# DASH.net
KiCad netlist of a schematic drawn in Altium Designer
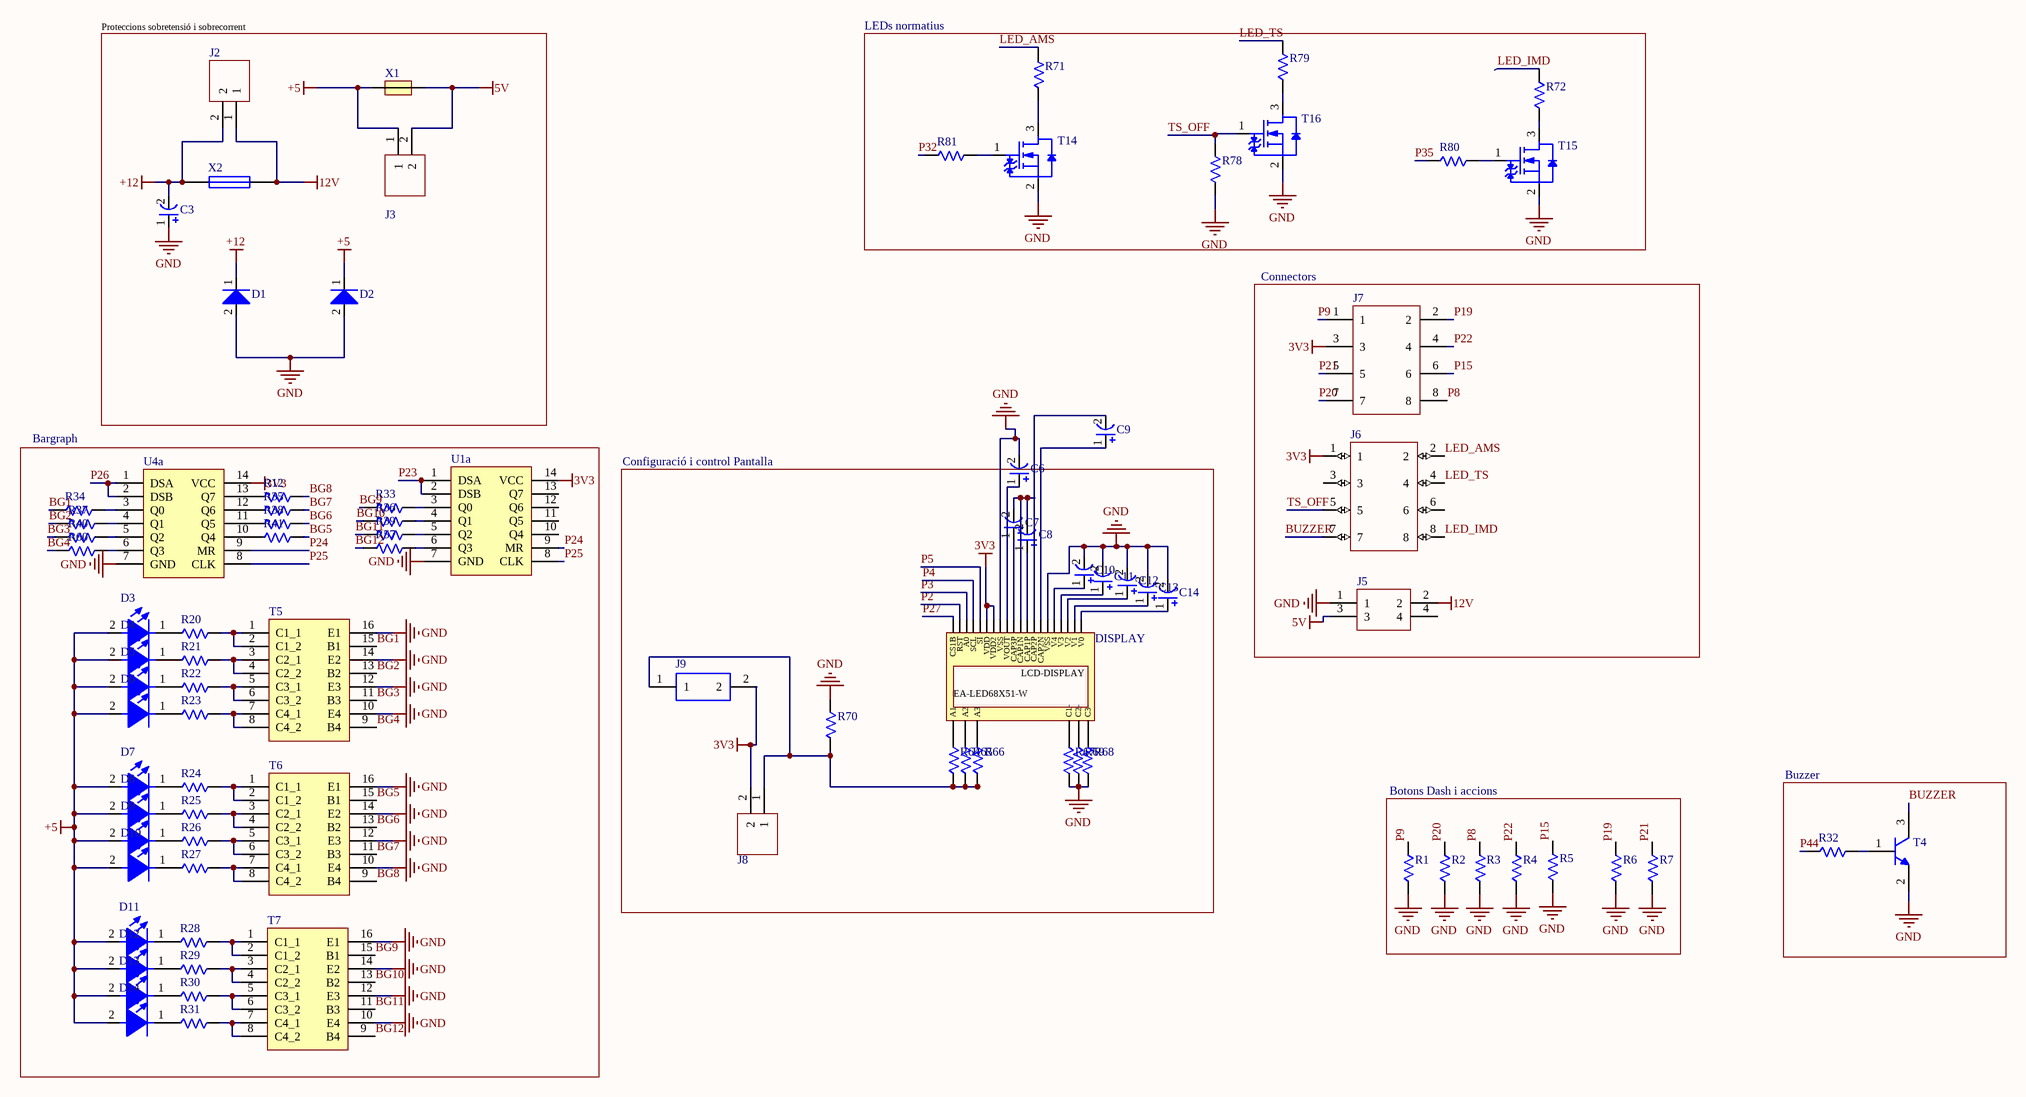
[diagram p0: DASH.SchDoc]

(export (version "E")
  (design (tool "Eeschema 10.0.6"))
  (components
    (comp (ref "C3")
      (value "TAJA105K020RNJ")
      (footprint "Chip2PinSM127P600-8N(condensador)")
      (description "CAP TANT 100nF 20V 10% 1206")
      (fields (field (name "TOLERANCE") "20%") (field (name "VOLTAGE") "20V"))
      (libsource (lib "DASH1_Schlib1") (part "CONDENSADOR 100nF"))
    )
    (comp (ref "C6")
      (value "TAJA105K020RNJ")
      (footprint "Chip2PinSM127P600-8N(condensador)")
      (description "CAP TANT 1uF 20V 10% 1206")
      (fields (field (name "TOLERANCE") "20%") (field (name "VOLTAGE") "20V"))
      (libsource (lib "DASH1_Schlib1") (part "CONDENSADOR 1uF"))
    )
    (comp (ref "C7")
      (value "TAJA105K020RNJ")
      (footprint "Chip2PinSM127P600-8N(condensador)")
      (description "CAP TANT 1uF 20V 10% 1206")
      (fields (field (name "TOLERANCE") "20%") (field (name "VOLTAGE") "20V"))
      (libsource (lib "DASH1_Schlib1") (part "CONDENSADOR 1uF"))
    )
    (comp (ref "C8")
      (value "TAJA105K020RNJ")
      (footprint "Chip2PinSM127P600-8N(condensador)")
      (description "CAP TANT 1uF 20V 10% 1206")
      (fields (field (name "TOLERANCE") "20%") (field (name "VOLTAGE") "20V"))
      (libsource (lib "DASH1_Schlib1") (part "CONDENSADOR 1uF"))
    )
    (comp (ref "C9")
      (value "TAJA105K020RNJ")
      (footprint "Chip2PinSM127P600-8N(condensador)")
      (description "CAP TANT 1uF 20V 10% 1206")
      (fields (field (name "TOLERANCE") "20%") (field (name "VOLTAGE") "20V"))
      (libsource (lib "DASH1_Schlib1") (part "CONDENSADOR 1uF"))
    )
    (comp (ref "C10")
      (value "TAJA105K020RNJ")
      (footprint "Chip2PinSM127P600-8N(condensador)")
      (description "CAP TANT 1uF 20V 10% 1206")
      (fields (field (name "TOLERANCE") "20%") (field (name "VOLTAGE") "20V"))
      (libsource (lib "DASH1_Schlib1") (part "CONDENSADOR 1uF"))
    )
    (comp (ref "C11")
      (value "TAJA105K020RNJ")
      (footprint "Chip2PinSM127P600-8N(condensador)")
      (description "CAP TANT 1uF 20V 10% 1206")
      (fields (field (name "TOLERANCE") "20%") (field (name "VOLTAGE") "20V"))
      (libsource (lib "DASH1_Schlib1") (part "CONDENSADOR 1uF"))
    )
    (comp (ref "C12")
      (value "TAJA105K020RNJ")
      (footprint "Chip2PinSM127P600-8N(condensador)")
      (description "CAP TANT 1uF 20V 10% 1206")
      (fields (field (name "TOLERANCE") "20%") (field (name "VOLTAGE") "20V"))
      (libsource (lib "DASH1_Schlib1") (part "CONDENSADOR 1uF"))
    )
    (comp (ref "C13")
      (value "TAJA105K020RNJ")
      (footprint "Chip2PinSM127P600-8N(condensador)")
      (description "CAP TANT 1uF 20V 10% 1206")
      (fields (field (name "TOLERANCE") "20%") (field (name "VOLTAGE") "20V"))
      (libsource (lib "DASH1_Schlib1") (part "CONDENSADOR 1uF"))
    )
    (comp (ref "C14")
      (value "TAJA105K020RNJ")
      (footprint "Chip2PinSM127P600-8N(condensador)")
      (description "CAP TANT 1uF 20V 10% 1206")
      (fields (field (name "TOLERANCE") "20%") (field (name "VOLTAGE") "20V"))
      (libsource (lib "DASH1_Schlib1") (part "CONDENSADOR 1uF"))
    )
    (comp (ref "D1")
      (value "SMAJ12CA")
      (footprint "Diode")
      (description "TVS DIODE 12V 19.9V DO214AC")
      (libsource (lib "DASH1_Schlib1") (part "DIODE"))
    )
    (comp (ref "D2")
      (value "SMAJ12CA")
      (footprint "Diode")
      (description "TVS DIODE 12V 19.9V DO214AC")
      (libsource (lib "DASH1_Schlib1") (part "DIODE"))
    )
    (comp (ref "D3")
      (value "150141GS73100")
      (footprint "Chip2PinSM127P600-8N(Buzz)")
      (description "WURTH ELEKTRONIK   150141GS73100   LED, 1411, GREEN, 1000MCD, 525NM")
      (libsource (lib "DASH1_Schlib1") (part "LED"))
    )
    (comp (ref "D4")
      (value "150141GS73100")
      (footprint "Chip2PinSM127P600-8N(Buzz)")
      (description "WURTH ELEKTRONIK   150141GS73100   LED, 1411, GREEN, 1000MCD, 525NM")
      (libsource (lib "DASH1_Schlib1") (part "LED"))
    )
    (comp (ref "D5")
      (value "150141GS73100")
      (footprint "Chip2PinSM127P600-8N(Buzz)")
      (description "WURTH ELEKTRONIK   150141GS73100   LED, 1411, GREEN, 1000MCD, 525NM")
      (libsource (lib "DASH1_Schlib1") (part "LED"))
    )
    (comp (ref "D6")
      (value "150141GS73100")
      (footprint "Chip2PinSM127P600-8N(Buzz)")
      (description "WURTH ELEKTRONIK   150141GS73100   LED, 1411, GREEN, 1000MCD, 525NM")
      (libsource (lib "DASH1_Schlib1") (part "LED"))
    )
    (comp (ref "D7")
      (value "150141GS73100")
      (footprint "Chip2PinSM127P600-8N(Buzz)")
      (description "WURTH ELEKTRONIK   150141GS73100   LED, 1411, GREEN, 1000MCD, 525NM")
      (libsource (lib "DASH1_Schlib1") (part "LED"))
    )
    (comp (ref "D8")
      (value "150141GS73100")
      (footprint "Chip2PinSM127P600-8N(Buzz)")
      (description "WURTH ELEKTRONIK   150141GS73100   LED, 1411, GREEN, 1000MCD, 525NM")
      (libsource (lib "DASH1_Schlib1") (part "LED"))
    )
    (comp (ref "D9")
      (value "150141GS73100")
      (footprint "Chip2PinSM127P600-8N(Buzz)")
      (description "WURTH ELEKTRONIK   150141GS73100   LED, 1411, GREEN, 1000MCD, 525NM")
      (libsource (lib "DASH1_Schlib1") (part "LED"))
    )
    (comp (ref "D10")
      (value "150141GS73100")
      (footprint "Chip2PinSM127P600-8N(Buzz)")
      (description "WURTH ELEKTRONIK   150141GS73100   LED, 1411, GREEN, 1000MCD, 525NM")
      (libsource (lib "DASH1_Schlib1") (part "LED"))
    )
    (comp (ref "D11")
      (value "150141GS73100")
      (footprint "Chip2PinSM127P600-8N(Buzz)")
      (description "WURTH ELEKTRONIK   150141GS73100   LED, 1411, GREEN, 1000MCD, 525NM")
      (libsource (lib "DASH1_Schlib1") (part "LED"))
    )
    (comp (ref "D12")
      (value "150141GS73100")
      (footprint "Chip2PinSM127P600-8N(Buzz)")
      (description "WURTH ELEKTRONIK   150141GS73100   LED, 1411, GREEN, 1000MCD, 525NM")
      (libsource (lib "DASH1_Schlib1") (part "LED"))
    )
    (comp (ref "D13")
      (value "150141GS73100")
      (footprint "Chip2PinSM127P600-8N(Buzz)")
      (description "WURTH ELEKTRONIK   150141GS73100   LED, 1411, GREEN, 1000MCD, 525NM")
      (libsource (lib "DASH1_Schlib1") (part "LED"))
    )
    (comp (ref "D14")
      (value "150141GS73100")
      (footprint "Chip2PinSM127P600-8N(Buzz)")
      (description "WURTH ELEKTRONIK   150141GS73100   LED, 1411, GREEN, 1000MCD, 525NM")
      (libsource (lib "DASH1_Schlib1") (part "LED"))
    )
    (comp (ref "DISPLAY")
      (value "M20-7820442")
      (footprint "DISPLAY")
      (description "2.54mm (0.1\") Pitch SIL Vertical PC Tail Socket Assembly, selective gold + tin, 4 contacts")
      (libsource (lib "DASH1_Schlib1") (part "DISPLAY"))
    )
    (comp (ref "J2")
      (value "68001-202HLF")
      (footprint "J2")
      (description "CONN HEADER VERT 2POS 2.54MM")
      (libsource (lib "") (part "HEADER_1"))
    )
    (comp (ref "J3")
      (value "68001-202HLF")
      (footprint "J3")
      (description "CONN HEADER VERT 2POS 2.54MM")
      (libsource (lib "DASH1_Schlib1") (part "HEADER"))
    )
    (comp (ref "J5")
      (value "1053141104")
      (footprint "J5")
      (description "NANO-FIT RIGHT ANGLE HEADER, TH")
      (libsource (lib "DASH1_Schlib1") (part "HEADER_J5"))
    )
    (comp (ref "J6")
      (value "43045-0800")
      (footprint "J6")
      (description "CONN HEADER R/A 8POS 3MM")
      (libsource (lib "DASH1_Schlib1") (part "HEADER_J6"))
    )
    (comp (ref "J7")
      (value "105314-1108")
      (footprint "J7")
      (description "Conn Power HDR 8 POS 2.5mm Solder RA Thru-Hole 8 Terminal 1 Port Nano-Fit Tray")
      (libsource (lib "DASH1_Schlib1") (part "HEADER_J7"))
    )
    (comp (ref "J8")
      (value "68001-202HLF")
      (footprint "J8")
      (description "CONN HEADER VERT 2POS 2.54MM")
      (libsource (lib "") (part "HEADER_2"))
    )
    (comp (ref "J9")
      (value "105313-1202")
      (footprint "J9")
      (description "CONN HEADER R/A 2POS 2.5MM")
      (libsource (lib "DASH1_Schlib1") (part "HEADER_J9"))
    )
    (comp (ref "R1")
      (value "CRCW120610K0JNTA-ND")
      (footprint "ERJ-8GEYJ102V")
      (description "RES SMD 10K OHM 5% 1/4W 1206")
      (fields (field (name "TOLERANCE") "5%"))
      (libsource (lib "DASH1_Schlib1") (part "RESISTOR 10K"))
    )
    (comp (ref "R2")
      (value "CRCW120610K0JNTA-ND")
      (footprint "ERJ-8GEYJ102V")
      (description "RES SMD 10K OHM 5% 1/4W 1206")
      (fields (field (name "TOLERANCE") "5%"))
      (libsource (lib "DASH1_Schlib1") (part "RESISTOR 10K"))
    )
    (comp (ref "R3")
      (value "CRCW120610K0JNTA-ND")
      (footprint "ERJ-8GEYJ102V")
      (description "RES SMD 10K OHM 5% 1/4W 1206")
      (fields (field (name "TOLERANCE") "5%"))
      (libsource (lib "DASH1_Schlib1") (part "RESISTOR 10K"))
    )
    (comp (ref "R4")
      (value "CRCW120610K0JNTA-ND")
      (footprint "ERJ-8GEYJ102V")
      (description "RES SMD 10K OHM 5% 1/4W 1206")
      (fields (field (name "TOLERANCE") "5%"))
      (libsource (lib "DASH1_Schlib1") (part "RESISTOR 10K"))
    )
    (comp (ref "R5")
      (value "CRCW120610K0JNTA-ND")
      (footprint "ERJ-8GEYJ102V")
      (description "RES SMD 10K OHM 5% 1/4W 1206")
      (fields (field (name "TOLERANCE") "5%"))
      (libsource (lib "DASH1_Schlib1") (part "RESISTOR 10K"))
    )
    (comp (ref "R6")
      (value "CRCW120610K0JNTA-ND")
      (footprint "ERJ-8GEYJ102V")
      (description "RES SMD 10K OHM 5% 1/4W 1206")
      (fields (field (name "TOLERANCE") "5%"))
      (libsource (lib "DASH1_Schlib1") (part "RESISTOR 10K"))
    )
    (comp (ref "R7")
      (value "CRCW120610K0JNTA-ND")
      (footprint "ERJ-8GEYJ102V")
      (description "RES SMD 10K OHM 5% 1/4W 1206")
      (fields (field (name "TOLERANCE") "5%"))
      (libsource (lib "DASH1_Schlib1") (part "RESISTOR 10K"))
    )
    (comp (ref "R12")
      (value "ERJ-8GEYJ102V")
      (footprint "ERJ-8GEYJ102V")
      (description "Res Thick Film 1206(3216) 1K Ohm 5% 1/4W 200ppm/C Molded SMD Punched Carrier T/R")
      (fields (field (name "TOLERANCE") "5%"))
      (libsource (lib "DASH1_Schlib1") (part "RESISTOR 1K"))
    )
    (comp (ref "R20")
      (value "ERJ-8GEYJ151V")
      (footprint "ERJ-8GEYJ102V")
      (description "RES SMD 150 OHM 5% 1/4W 1206")
      (fields (field (name "TOLERANCE") "5%"))
      (libsource (lib "DASH1_Schlib1") (part "RESISTOR 150R"))
    )
    (comp (ref "R21")
      (value "ERJ-8GEYJ151V")
      (footprint "ERJ-8GEYJ102V")
      (description "RES SMD 150 OHM 5% 1/4W 1206")
      (fields (field (name "TOLERANCE") "5%"))
      (libsource (lib "DASH1_Schlib1") (part "RESISTOR 150R"))
    )
    (comp (ref "R22")
      (value "ERJ-8GEYJ151V")
      (footprint "ERJ-8GEYJ102V")
      (description "RES SMD 150 OHM 5% 1/4W 1206")
      (fields (field (name "TOLERANCE") "5%"))
      (libsource (lib "DASH1_Schlib1") (part "RESISTOR 150R"))
    )
    (comp (ref "R23")
      (value "ERJ-8GEYJ151V")
      (footprint "ERJ-8GEYJ102V")
      (description "RES SMD 150 OHM 5% 1/4W 1206")
      (fields (field (name "TOLERANCE") "5%"))
      (libsource (lib "DASH1_Schlib1") (part "RESISTOR 150R"))
    )
    (comp (ref "R24")
      (value "ERJ-8GEYJ151V")
      (footprint "ERJ-8GEYJ102V")
      (description "RES SMD 150 OHM 5% 1/4W 1206")
      (fields (field (name "TOLERANCE") "5%"))
      (libsource (lib "DASH1_Schlib1") (part "RESISTOR 150R"))
    )
    (comp (ref "R25")
      (value "ERJ-8GEYJ151V")
      (footprint "ERJ-8GEYJ102V")
      (description "RES SMD 150 OHM 5% 1/4W 1206")
      (fields (field (name "TOLERANCE") "5%"))
      (libsource (lib "DASH1_Schlib1") (part "RESISTOR 150R"))
    )
    (comp (ref "R26")
      (value "ERJ-8GEYJ151V")
      (footprint "ERJ-8GEYJ102V")
      (description "RES SMD 150 OHM 5% 1/4W 1206")
      (fields (field (name "TOLERANCE") "5%"))
      (libsource (lib "DASH1_Schlib1") (part "RESISTOR 150R"))
    )
    (comp (ref "R27")
      (value "ERJ-8GEYJ151V")
      (footprint "ERJ-8GEYJ102V")
      (description "RES SMD 150 OHM 5% 1/4W 1206")
      (fields (field (name "TOLERANCE") "5%"))
      (libsource (lib "DASH1_Schlib1") (part "RESISTOR 150R"))
    )
    (comp (ref "R28")
      (value "ERJ-8GEYJ151V")
      (footprint "ERJ-8GEYJ102V")
      (description "RES SMD 150 OHM 5% 1/4W 1206")
      (fields (field (name "TOLERANCE") "5%"))
      (libsource (lib "DASH1_Schlib1") (part "RESISTOR 150R"))
    )
    (comp (ref "R29")
      (value "ERJ-8GEYJ151V")
      (footprint "ERJ-8GEYJ102V")
      (description "RES SMD 150 OHM 5% 1/4W 1206")
      (fields (field (name "TOLERANCE") "5%"))
      (libsource (lib "DASH1_Schlib1") (part "RESISTOR 150R"))
    )
    (comp (ref "R30")
      (value "ERJ-8GEYJ151V")
      (footprint "ERJ-8GEYJ102V")
      (description "RES SMD 150 OHM 5% 1/4W 1206")
      (fields (field (name "TOLERANCE") "5%"))
      (libsource (lib "DASH1_Schlib1") (part "RESISTOR 150R"))
    )
    (comp (ref "R31")
      (value "ERJ-8GEYJ151V")
      (footprint "ERJ-8GEYJ102V")
      (description "RES SMD 150 OHM 5% 1/4W 1206")
      (fields (field (name "TOLERANCE") "5%"))
      (libsource (lib "DASH1_Schlib1") (part "RESISTOR 150R"))
    )
    (comp (ref "R32")
      (value "ERJ-8GEYJ102V")
      (footprint "ERJ-8GEYJ102V")
      (description "Res Thick Film 1206(3216) 1K Ohm 5% 1/4W 200ppm/C Molded SMD Punched Carrier T/R")
      (fields (field (name "TOLERANCE") "5%"))
      (libsource (lib "DASH1_Schlib1") (part "RESISTOR 1K"))
    )
    (comp (ref "R33")
      (value "ERJ-8GEYJ102V")
      (footprint "ERJ-8GEYJ102V")
      (description "Res Thick Film 1206(3216) 1K Ohm 5% 1/4W 200ppm/C Molded SMD Punched Carrier T/R")
      (fields (field (name "TOLERANCE") "5%"))
      (libsource (lib "DASH1_Schlib1") (part "RESISTOR 1K"))
    )
    (comp (ref "R34")
      (value "ERJ-8GEYJ102V")
      (footprint "ERJ-8GEYJ102V")
      (description "Res Thick Film 1206(3216) 1K Ohm 5% 1/4W 200ppm/C Molded SMD Punched Carrier T/R")
      (fields (field (name "TOLERANCE") "5%"))
      (libsource (lib "DASH1_Schlib1") (part "RESISTOR 1K"))
    )
    (comp (ref "R35")
      (value "ERJ-8GEYJ102V")
      (footprint "ERJ-8GEYJ102V")
      (description "Res Thick Film 1206(3216) 1K Ohm 5% 1/4W 200ppm/C Molded SMD Punched Carrier T/R")
      (fields (field (name "TOLERANCE") "5%"))
      (libsource (lib "DASH1_Schlib1") (part "RESISTOR 1K"))
    )
    (comp (ref "R36")
      (value "ERJ-8GEYJ102V")
      (footprint "ERJ-8GEYJ102V")
      (description "Res Thick Film 1206(3216) 1K Ohm 5% 1/4W 200ppm/C Molded SMD Punched Carrier T/R")
      (fields (field (name "TOLERANCE") "5%"))
      (libsource (lib "DASH1_Schlib1") (part "RESISTOR 1K"))
    )
    (comp (ref "R37")
      (value "ERJ-8GEYJ102V")
      (footprint "ERJ-8GEYJ102V")
      (description "Res Thick Film 1206(3216) 1K Ohm 5% 1/4W 200ppm/C Molded SMD Punched Carrier T/R")
      (fields (field (name "TOLERANCE") "5%"))
      (libsource (lib "DASH1_Schlib1") (part "RESISTOR 1K"))
    )
    (comp (ref "R38")
      (value "ERJ-8GEYJ102V")
      (footprint "ERJ-8GEYJ102V")
      (description "Res Thick Film 1206(3216) 1K Ohm 5% 1/4W 200ppm/C Molded SMD Punched Carrier T/R")
      (fields (field (name "TOLERANCE") "5%"))
      (libsource (lib "DASH1_Schlib1") (part "RESISTOR 1K"))
    )
    (comp (ref "R39")
      (value "ERJ-8GEYJ102V")
      (footprint "ERJ-8GEYJ102V")
      (description "Res Thick Film 1206(3216) 1K Ohm 5% 1/4W 200ppm/C Molded SMD Punched Carrier T/R")
      (fields (field (name "TOLERANCE") "5%"))
      (libsource (lib "DASH1_Schlib1") (part "RESISTOR 1K"))
    )
    (comp (ref "R40")
      (value "ERJ-8GEYJ102V")
      (footprint "ERJ-8GEYJ102V")
      (description "Res Thick Film 1206(3216) 1K Ohm 5% 1/4W 200ppm/C Molded SMD Punched Carrier T/R")
      (fields (field (name "TOLERANCE") "5%"))
      (libsource (lib "DASH1_Schlib1") (part "RESISTOR 1K"))
    )
    (comp (ref "R41")
      (value "ERJ-8GEYJ102V")
      (footprint "ERJ-8GEYJ102V")
      (description "Res Thick Film 1206(3216) 1K Ohm 5% 1/4W 200ppm/C Molded SMD Punched Carrier T/R")
      (fields (field (name "TOLERANCE") "5%"))
      (libsource (lib "DASH1_Schlib1") (part "RESISTOR 1K"))
    )
    (comp (ref "R57")
      (value "ERJ-8GEYJ102V")
      (footprint "ERJ-8GEYJ102V")
      (description "Res Thick Film 1206(3216) 1K Ohm 5% 1/4W 200ppm/C Molded SMD Punched Carrier T/R")
      (fields (field (name "TOLERANCE") "5%"))
      (libsource (lib "DASH1_Schlib1") (part "RESISTOR 1K"))
    )
    (comp (ref "R60")
      (value "ERJ-8GEYJ102V")
      (footprint "ERJ-8GEYJ102V")
      (description "Res Thick Film 1206(3216) 1K Ohm 5% 1/4W 200ppm/C Molded SMD Punched Carrier T/R")
      (fields (field (name "TOLERANCE") "5%"))
      (libsource (lib "DASH1_Schlib1") (part "RESISTOR 1K"))
    )
    (comp (ref "R64")
      (value "ERJ-8GEYJ102V")
      (footprint "ERJ-8GEYJ102V")
      (description "Res Thick Film 1206(3216) 70 Ohm 5% 1/4W 200ppm/C Molded SMD Punched Carrier T/R")
      (fields (field (name "TOLERANCE") "5%"))
      (libsource (lib "DASH1_Schlib1") (part "RESISTOR 70R"))
    )
    (comp (ref "R65")
      (value "ERJ-8GEYJ102V")
      (footprint "ERJ-8GEYJ102V")
      (description "Res Thick Film 1206(3216) 70 Ohm 5% 1/4W 200ppm/C Molded SMD Punched Carrier T/R")
      (fields (field (name "TOLERANCE") "5%"))
      (libsource (lib "DASH1_Schlib1") (part "RESISTOR 70R"))
    )
    (comp (ref "R66")
      (value "ERJ-8GEYJ102V")
      (footprint "ERJ-8GEYJ102V")
      (description "Res Thick Film 1206(3216) 70 Ohm 5% 1/4W 200ppm/C Molded SMD Punched Carrier T/R")
      (fields (field (name "TOLERANCE") "5%"))
      (libsource (lib "DASH1_Schlib1") (part "RESISTOR 70R"))
    )
    (comp (ref "R67")
      (value "ERJ-8GEYJ102V")
      (footprint "ERJ-8GEYJ102V")
      (description "Res Thick Film 1206(3216) 70 Ohm 5% 1/4W 200ppm/C Molded SMD Punched Carrier T/R")
      (fields (field (name "TOLERANCE") "5%"))
      (libsource (lib "DASH1_Schlib1") (part "RESISTOR 70R"))
    )
    (comp (ref "R68")
      (value "ERJ-8GEYJ102V")
      (footprint "ERJ-8GEYJ102V")
      (description "Res Thick Film 1206(3216) 70 Ohm 5% 1/4W 200ppm/C Molded SMD Punched Carrier T/R")
      (fields (field (name "TOLERANCE") "5%"))
      (libsource (lib "DASH1_Schlib1") (part "RESISTOR 70R"))
    )
    (comp (ref "R69")
      (value "ERJ-8GEYJ102V")
      (footprint "ERJ-8GEYJ102V")
      (description "Res Thick Film 1206(3216) 70 Ohm 5% 1/4W 200ppm/C Molded SMD Punched Carrier T/R")
      (fields (field (name "TOLERANCE") "5%"))
      (libsource (lib "DASH1_Schlib1") (part "RESISTOR 70R"))
    )
    (comp (ref "R70")
      (value "CRCW120610K0JNTA-ND")
      (footprint "ERJ-8GEYJ102V")
      (description "RES SMD 10K OHM 5% 1/4W 1206")
      (fields (field (name "TOLERANCE") "5%"))
      (libsource (lib "DASH1_Schlib1") (part "RESISTOR 10K"))
    )
    (comp (ref "R71")
      (value "ERJ-8GEYJ151V")
      (footprint "ERJ-8GEYJ102V")
      (description "RES SMD 150 OHM 5% 1/4W 1206")
      (fields (field (name "TOLERANCE") "5%"))
      (libsource (lib "DASH1_Schlib1") (part "RESISTOR 150R"))
    )
    (comp (ref "R72")
      (value "ERJ-8GEYJ151V")
      (footprint "ERJ-8GEYJ102V")
      (description "RES SMD 150 OHM 5% 1/4W 1206")
      (fields (field (name "TOLERANCE") "5%"))
      (libsource (lib "DASH1_Schlib1") (part "RESISTOR 150R"))
    )
    (comp (ref "R78")
      (value "CRCW120610K0JNTA-ND")
      (footprint "ERJ-8GEYJ102V")
      (description "RES SMD 10K OHM 5% 1/4W 1206")
      (fields (field (name "TOLERANCE") "5%"))
      (libsource (lib "DASH1_Schlib1") (part "RESISTOR 10K"))
    )
    (comp (ref "R79")
      (value "ERJ-8GEYJ151V")
      (footprint "ERJ-8GEYJ102V")
      (description "RES SMD 150 OHM 5% 1/4W 1206")
      (fields (field (name "TOLERANCE") "5%"))
      (libsource (lib "DASH1_Schlib1") (part "RESISTOR 150R"))
    )
    (comp (ref "R80")
      (value "ERJ-8GEYJ102V")
      (footprint "ERJ-8GEYJ102V")
      (description "Res Thick Film 1206(3216) 1K Ohm 5% 1/4W 200ppm/C Molded SMD Punched Carrier T/R")
      (fields (field (name "TOLERANCE") "5%"))
      (libsource (lib "DASH1_Schlib1") (part "RESISTOR 1K"))
    )
    (comp (ref "R81")
      (value "ERJ-8GEYJ102V")
      (footprint "ERJ-8GEYJ102V")
      (description "Res Thick Film 1206(3216) 1K Ohm 5% 1/4W 200ppm/C Molded SMD Punched Carrier T/R")
      (fields (field (name "TOLERANCE") "5%"))
      (libsource (lib "DASH1_Schlib1") (part "RESISTOR 1K"))
    )
    (comp (ref "T4")
      (value "BC817-25LT1G")
      (footprint "SOT190P240X100-3N")
      (description "TRANS NPN 45V 0.5A SOT23")
      (libsource (lib "DASH1_Schlib1") (part "TRANSISTOR_BUZZ"))
    )
    (comp (ref "T5")
      (value "MMPQ2222A")
      (footprint "SOP127P600-8N(MMPQ2222A)")
      (description "TRANS 4NPN 40V 0.5A 16SOIC")
      (libsource (lib "DASH1_Schlib1") (part "MMPQ2222A"))
    )
    (comp (ref "T6")
      (value "MMPQ2222A")
      (footprint "SOP127P600-8N(MMPQ2222A)")
      (description "TRANS 4NPN 40V 0.5A 16SOIC")
      (libsource (lib "DASH1_Schlib1") (part "MMPQ2222A"))
    )
    (comp (ref "T7")
      (value "MMPQ2222A")
      (footprint "SOP127P600-8N(MMPQ2222A)")
      (description "TRANS 4NPN 40V 0.5A 16SOIC")
      (libsource (lib "DASH1_Schlib1") (part "MMPQ2222A"))
    )
    (comp (ref "T14")
      (value "CPH3455-TL-H")
      (footprint "SOT190P280X90-3N")
      (description "MOSFET N-CH 35V 3A CPH3")
      (libsource (lib "DASH1_Schlib1") (part "TRANSISTOR"))
    )
    (comp (ref "T15")
      (value "CPH3455-TL-H")
      (footprint "SOT190P280X90-3N")
      (description "MOSFET N-CH 35V 3A CPH3")
      (libsource (lib "DASH1_Schlib1") (part "TRANSISTOR"))
    )
    (comp (ref "T16")
      (value "CPH3455-TL-H")
      (footprint "SOT190P280X90-3N")
      (description "MOSFET N-CH 35V 3A CPH3")
      (libsource (lib "DASH1_Schlib1") (part "TRANSISTOR"))
    )
    (comp (ref "U1a")
      (value "SN74HC164D")
      (footprint "SOP127P600-8N")
      (description "IC, SHIFT REGISTER, SMD, 74HC164")
      (libsource (lib "DASH1_Schlib1") (part "SN74HC164D"))
    )
    (comp (ref "U4a")
      (value "SN74HC164D")
      (footprint "SOP127P600-8N")
      (description "IC, SHIFT REGISTER, SMD, 74HC164")
      (libsource (lib "DASH1_Schlib1") (part "SN74HC164D"))
    )
    (comp (ref "X1") (value "FUSE 3A") (footprint "Fuse") (libsource (lib "DASH1_Schlib1") (part "FUSE 3A")))
    (comp (ref "X2")
      (value "Fuse 1A")
      (footprint "Fuse")
      (description "Fuse")
      (fields (field (name "PUBLISHER") "Altium Limited"))
      (libsource (lib "Miscellaneous Devices") (part "Fuse 1"))
    )
  )
  (nets
    (net (code "1") (name "+5") (class "Default")
      (node (ref "D10") (pin "2") (pinfunction "ANODE_2") (pintype "passive"))
      (node (ref "D11") (pin "2") (pinfunction "ANODE_2") (pintype "passive"))
      (node (ref "D12") (pin "2") (pinfunction "ANODE_2") (pintype "passive"))
      (node (ref "D13") (pin "2") (pinfunction "ANODE_2") (pintype "passive"))
      (node (ref "D14") (pin "2") (pinfunction "ANODE_2") (pintype "passive"))
      (node (ref "D2") (pin "1") (pinfunction "catode_1") (pintype "passive"))
      (node (ref "D3") (pin "2") (pinfunction "ANODE_2") (pintype "passive"))
      (node (ref "D4") (pin "2") (pinfunction "ANODE_2") (pintype "passive"))
      (node (ref "D5") (pin "2") (pinfunction "ANODE_2") (pintype "passive"))
      (node (ref "D6") (pin "2") (pinfunction "ANODE_2") (pintype "passive"))
      (node (ref "D7") (pin "2") (pinfunction "ANODE_2") (pintype "passive"))
      (node (ref "D8") (pin "2") (pinfunction "ANODE_2") (pintype "passive"))
      (node (ref "D9") (pin "2") (pinfunction "ANODE_2") (pintype "passive"))
      (node (ref "J3") (pin "1") (pinfunction "1_1") (pintype "passive"))
      (node (ref "X1") (pin "1") (pinfunction "1_1") (pintype "passive"))
    )
    (net (code "2") (name "+12") (class "Default")
      (node (ref "C3") (pin "2") (pinfunction "2_2") (pintype "passive"))
      (node (ref "D1") (pin "1") (pinfunction "catode_1") (pintype "passive"))
      (node (ref "J2") (pin "2") (pinfunction "2_2") (pintype "passive"))
      (node (ref "X2") (pin "1") (pinfunction "1_1") (pintype "passive"))
    )
    (net (code "4") (name "/BG1") (class "Default")
      (node (ref "R34") (pin "1") (pinfunction "1_1") (pintype "passive"))
      (node (ref "T5") (pin "15") (pinfunction "B1_15") (pintype "passive"))
    )
    (net (code "5") (name "/BG2") (class "Default")
      (node (ref "R37") (pin "1") (pinfunction "1_1") (pintype "passive"))
      (node (ref "T5") (pin "13") (pinfunction "B2_13") (pintype "passive"))
    )
    (net (code "6") (name "/BG3") (class "Default")
      (node (ref "R40") (pin "1") (pinfunction "1_1") (pintype "passive"))
      (node (ref "T5") (pin "11") (pinfunction "B3_11") (pintype "passive"))
    )
    (net (code "7") (name "/BG4") (class "Default")
      (node (ref "R60") (pin "1") (pinfunction "1_1") (pintype "passive"))
      (node (ref "T5") (pin "9") (pinfunction "B4_9") (pintype "passive"))
    )
    (net (code "8") (name "/BG5") (class "Default")
      (node (ref "R41") (pin "2") (pinfunction "2_2") (pintype "passive"))
      (node (ref "T6") (pin "15") (pinfunction "B1_15") (pintype "passive"))
    )
    (net (code "9") (name "/BG6") (class "Default")
      (node (ref "R38") (pin "2") (pinfunction "2_2") (pintype "passive"))
      (node (ref "T6") (pin "13") (pinfunction "B2_13") (pintype "passive"))
    )
    (net (code "10") (name "/BG7") (class "Default")
      (node (ref "R35") (pin "2") (pinfunction "2_2") (pintype "passive"))
      (node (ref "T6") (pin "11") (pinfunction "B3_11") (pintype "passive"))
    )
    (net (code "11") (name "/BG8") (class "Default")
      (node (ref "R12") (pin "2") (pinfunction "2_2") (pintype "passive"))
      (node (ref "T6") (pin "9") (pinfunction "B4_9") (pintype "passive"))
    )
    (net (code "12") (name "/BG9") (class "Default")
      (node (ref "R33") (pin "1") (pinfunction "1_1") (pintype "passive"))
      (node (ref "T7") (pin "15") (pinfunction "B1_15") (pintype "passive"))
    )
    (net (code "13") (name "/BG10") (class "Default")
      (node (ref "R36") (pin "1") (pinfunction "1_1") (pintype "passive"))
      (node (ref "T7") (pin "13") (pinfunction "B2_13") (pintype "passive"))
    )
    (net (code "14") (name "/BG11") (class "Default")
      (node (ref "R39") (pin "1") (pinfunction "1_1") (pintype "passive"))
      (node (ref "T7") (pin "11") (pinfunction "B3_11") (pintype "passive"))
    )
    (net (code "15") (name "/BG12") (class "Default")
      (node (ref "R57") (pin "1") (pinfunction "1_1") (pintype "passive"))
      (node (ref "T7") (pin "9") (pinfunction "B4_9") (pintype "passive"))
    )
    (net (code "16") (name "/BUZZER") (class "Default")
      (node (ref "J6") (pin "7") (pinfunction "7_7") (pintype "bidirectional"))
      (node (ref "T4") (pin "3") (pinfunction "Collector_3") (pintype "passive"))
    )
    (net (code "17") (name "/LED_AMS") (class "Default")
      (node (ref "J6") (pin "2") (pinfunction "2_2") (pintype "bidirectional"))
      (node (ref "R71") (pin "2") (pinfunction "2_2") (pintype "passive"))
    )
    (net (code "18") (name "/LED_IMD") (class "Default")
      (node (ref "J6") (pin "8") (pinfunction "8_8") (pintype "bidirectional"))
      (node (ref "R72") (pin "2") (pinfunction "2_2") (pintype "passive"))
    )
    (net (code "19") (name "/LED_TS") (class "Default")
      (node (ref "J6") (pin "4") (pinfunction "4_4") (pintype "bidirectional"))
      (node (ref "R79") (pin "2") (pinfunction "2_2") (pintype "passive"))
    )
    (net (code "20") (name "/P2") (class "Default")
      (node (ref "DISPLAY") (pin "39") (pinfunction "RST_39") (pintype "passive"))
    )
    (net (code "21") (name "/P3") (class "Default")
      (node (ref "DISPLAY") (pin "38") (pinfunction "A0_38") (pintype "passive"))
    )
    (net (code "22") (name "/P4") (class "Default")
      (node (ref "DISPLAY") (pin "37") (pinfunction "SCL_37") (pintype "passive"))
    )
    (net (code "23") (name "/P5") (class "Default")
      (node (ref "DISPLAY") (pin "36") (pinfunction "SI_36") (pintype "passive"))
    )
    (net (code "24") (name "/P8") (class "Default")
      (node (ref "J7") (pin "8") (pinfunction "8_8") (pintype "passive"))
      (node (ref "R3") (pin "2") (pinfunction "2_2") (pintype "passive"))
    )
    (net (code "25") (name "/P9") (class "Default")
      (node (ref "J7") (pin "1") (pinfunction "1_1") (pintype "passive"))
      (node (ref "R1") (pin "2") (pinfunction "2_2") (pintype "passive"))
    )
    (net (code "26") (name "/P15") (class "Default")
      (node (ref "J7") (pin "6") (pinfunction "6_6") (pintype "passive"))
      (node (ref "R5") (pin "2") (pinfunction "2_2") (pintype "passive"))
    )
    (net (code "27") (name "/P19") (class "Default")
      (node (ref "J7") (pin "2") (pinfunction "2_2") (pintype "passive"))
      (node (ref "R6") (pin "2") (pinfunction "2_2") (pintype "passive"))
    )
    (net (code "28") (name "/P20") (class "Default")
      (node (ref "J7") (pin "7") (pinfunction "7_7") (pintype "passive"))
      (node (ref "R2") (pin "2") (pinfunction "2_2") (pintype "passive"))
    )
    (net (code "29") (name "/P21") (class "Default")
      (node (ref "J7") (pin "5") (pinfunction "5_5") (pintype "passive"))
      (node (ref "R7") (pin "2") (pinfunction "2_2") (pintype "passive"))
    )
    (net (code "30") (name "/P22") (class "Default")
      (node (ref "J7") (pin "4") (pinfunction "4_4") (pintype "passive"))
      (node (ref "R4") (pin "2") (pinfunction "2_2") (pintype "passive"))
    )
    (net (code "31") (name "/P23") (class "Default")
      (node (ref "U1a") (pin "1") (pinfunction "DSA_1") (pintype "passive"))
      (node (ref "U1a") (pin "2") (pinfunction "DSB_2") (pintype "passive"))
    )
    (net (code "32") (name "/P24") (class "Default")
      (node (ref "U1a") (pin "9") (pinfunction "MR_9") (pintype "passive"))
      (node (ref "U4a") (pin "9") (pinfunction "MR_9") (pintype "passive"))
    )
    (net (code "33") (name "/P25") (class "Default")
      (node (ref "U1a") (pin "8") (pinfunction "CLK_8") (pintype "passive"))
      (node (ref "U4a") (pin "8") (pinfunction "CLK_8") (pintype "passive"))
    )
    (net (code "34") (name "/P26") (class "Default")
      (node (ref "U4a") (pin "1") (pinfunction "DSA_1") (pintype "passive"))
      (node (ref "U4a") (pin "2") (pinfunction "DSB_2") (pintype "passive"))
    )
    (net (code "35") (name "/P27") (class "Default")
      (node (ref "DISPLAY") (pin "40") (pinfunction "CS1B_40") (pintype "passive"))
    )
    (net (code "36") (name "/P32") (class "Default")
      (node (ref "R81") (pin "1") (pinfunction "1_1") (pintype "passive"))
    )
    (net (code "37") (name "/P35") (class "Default")
      (node (ref "R80") (pin "1") (pinfunction "1_1") (pintype "passive"))
    )
    (net (code "38") (name "/P44") (class "Default")
      (node (ref "R32") (pin "1") (pinfunction "1_1") (pintype "passive"))
    )
    (net (code "39") (name "/TS_OFF") (class "Default")
      (node (ref "J6") (pin "5") (pinfunction "5_5") (pintype "bidirectional"))
      (node (ref "R78") (pin "2") (pinfunction "2_2") (pintype "passive"))
      (node (ref "T16") (pin "1") (pinfunction "Gate_1") (pintype "passive"))
    )
    (net (code "40") (name "3V3") (class "Default")
      (node (ref "DISPLAY") (pin "34") (pinfunction "VDD2_34") (pintype "passive"))
      (node (ref "DISPLAY") (pin "35") (pinfunction "VDD_35") (pintype "passive"))
      (node (ref "J6") (pin "1") (pinfunction "1_1") (pintype "bidirectional"))
      (node (ref "J7") (pin "3") (pinfunction "3_3") (pintype "passive"))
      (node (ref "J8") (pin "2") (pinfunction "2_2") (pintype "passive"))
      (node (ref "J9") (pin "2") (pinfunction "2_2") (pintype "passive"))
      (node (ref "U1a") (pin "14") (pinfunction "VCC_14") (pintype "power_in"))
      (node (ref "U4a") (pin "14") (pinfunction "VCC_14") (pintype "power_in"))
    )
    (net (code "41") (name "5V") (class "Default")
      (node (ref "J3") (pin "2") (pinfunction "2_2") (pintype "passive"))
      (node (ref "J5") (pin "3") (pinfunction "3_3") (pintype "passive"))
      (node (ref "X1") (pin "2") (pinfunction "2_2") (pintype "passive"))
    )
    (net (code "42") (name "12V") (class "Default")
      (node (ref "J2") (pin "1") (pinfunction "1_1") (pintype "passive"))
      (node (ref "J5") (pin "2") (pinfunction "2_2") (pintype "passive"))
      (node (ref "X2") (pin "2") (pinfunction "2_2") (pintype "passive"))
    )
    (net (code "43") (name "GND") (class "Default")
      (node (ref "C10") (pin "2") (pinfunction "2_2") (pintype "passive"))
      (node (ref "C11") (pin "2") (pinfunction "2_2") (pintype "passive"))
      (node (ref "C12") (pin "2") (pinfunction "2_2") (pintype "passive"))
      (node (ref "C13") (pin "2") (pinfunction "2_2") (pintype "passive"))
      (node (ref "C14") (pin "2") (pinfunction "2_2") (pintype "passive"))
      (node (ref "C3") (pin "1") (pinfunction "1_1") (pintype "passive"))
      (node (ref "C6") (pin "2") (pinfunction "2_2") (pintype "passive"))
      (node (ref "D1") (pin "2") (pinfunction "anode_2") (pintype "passive"))
      (node (ref "D2") (pin "2") (pinfunction "anode_2") (pintype "passive"))
      (node (ref "DISPLAY") (pin "26") (pinfunction "VSS_26") (pintype "passive"))
      (node (ref "DISPLAY") (pin "33") (pinfunction "VSS_33") (pintype "passive"))
      (node (ref "J5") (pin "1") (pinfunction "1_1") (pintype "passive"))
      (node (ref "R1") (pin "1") (pinfunction "1_1") (pintype "passive"))
      (node (ref "R2") (pin "1") (pinfunction "1_1") (pintype "passive"))
      (node (ref "R3") (pin "1") (pinfunction "1_1") (pintype "passive"))
      (node (ref "R4") (pin "1") (pinfunction "1_1") (pintype "passive"))
      (node (ref "R5") (pin "1") (pinfunction "1_1") (pintype "passive"))
      (node (ref "R6") (pin "1") (pinfunction "1_1") (pintype "passive"))
      (node (ref "R67") (pin "2") (pinfunction "2_2") (pintype "passive"))
      (node (ref "R68") (pin "2") (pinfunction "2_2") (pintype "passive"))
      (node (ref "R69") (pin "2") (pinfunction "2_2") (pintype "passive"))
      (node (ref "R7") (pin "1") (pinfunction "1_1") (pintype "passive"))
      (node (ref "R70") (pin "2") (pinfunction "2_2") (pintype "passive"))
      (node (ref "R78") (pin "1") (pinfunction "1_1") (pintype "passive"))
      (node (ref "T14") (pin "2") (pinfunction "Source_2") (pintype "passive"))
      (node (ref "T15") (pin "2") (pinfunction "Source_2") (pintype "passive"))
      (node (ref "T16") (pin "2") (pinfunction "Source_2") (pintype "passive"))
      (node (ref "T4") (pin "2") (pinfunction "Emitter_2") (pintype "passive"))
      (node (ref "T5") (pin "10") (pinfunction "E4_10") (pintype "passive"))
      (node (ref "T5") (pin "12") (pinfunction "E3_12") (pintype "passive"))
      (node (ref "T5") (pin "14") (pinfunction "E2_14") (pintype "passive"))
      (node (ref "T5") (pin "16") (pinfunction "E1_16") (pintype "passive"))
      (node (ref "T6") (pin "10") (pinfunction "E4_10") (pintype "passive"))
      (node (ref "T6") (pin "12") (pinfunction "E3_12") (pintype "passive"))
      (node (ref "T6") (pin "14") (pinfunction "E2_14") (pintype "passive"))
      (node (ref "T6") (pin "16") (pinfunction "E1_16") (pintype "passive"))
      (node (ref "T7") (pin "10") (pinfunction "E4_10") (pintype "passive"))
      (node (ref "T7") (pin "12") (pinfunction "E3_12") (pintype "passive"))
      (node (ref "T7") (pin "14") (pinfunction "E2_14") (pintype "passive"))
      (node (ref "T7") (pin "16") (pinfunction "E1_16") (pintype "passive"))
      (node (ref "U1a") (pin "7") (pinfunction "GND_7") (pintype "passive"))
      (node (ref "U4a") (pin "7") (pinfunction "GND_7") (pintype "passive"))
    )
    (net (code "44") (name "Net-(D3-CATODE)") (class "Default")
      (node (ref "D3") (pin "1") (pinfunction "CATODE_1") (pintype "passive"))
      (node (ref "R20") (pin "1") (pinfunction "1_1") (pintype "passive"))
    )
    (net (code "45") (name "Net-(D4-CATODE)") (class "Default")
      (node (ref "D4") (pin "1") (pinfunction "CATODE_1") (pintype "passive"))
      (node (ref "R21") (pin "1") (pinfunction "1_1") (pintype "passive"))
    )
    (net (code "46") (name "Net-(D5-CATODE)") (class "Default")
      (node (ref "D5") (pin "1") (pinfunction "CATODE_1") (pintype "passive"))
      (node (ref "R22") (pin "1") (pinfunction "1_1") (pintype "passive"))
    )
    (net (code "47") (name "Net-(D6-CATODE)") (class "Default")
      (node (ref "D6") (pin "1") (pinfunction "CATODE_1") (pintype "passive"))
      (node (ref "R23") (pin "1") (pinfunction "1_1") (pintype "passive"))
    )
    (net (code "48") (name "Net-(D7-CATODE)") (class "Default")
      (node (ref "D7") (pin "1") (pinfunction "CATODE_1") (pintype "passive"))
      (node (ref "R24") (pin "1") (pinfunction "1_1") (pintype "passive"))
    )
    (net (code "49") (name "Net-(D8-CATODE)") (class "Default")
      (node (ref "D8") (pin "1") (pinfunction "CATODE_1") (pintype "passive"))
      (node (ref "R25") (pin "1") (pinfunction "1_1") (pintype "passive"))
    )
    (net (code "50") (name "Net-(D9-CATODE)") (class "Default")
      (node (ref "D9") (pin "1") (pinfunction "CATODE_1") (pintype "passive"))
      (node (ref "R26") (pin "1") (pinfunction "1_1") (pintype "passive"))
    )
    (net (code "51") (name "Net-(D10-CATODE)") (class "Default")
      (node (ref "D10") (pin "1") (pinfunction "CATODE_1") (pintype "passive"))
      (node (ref "R27") (pin "1") (pinfunction "1_1") (pintype "passive"))
    )
    (net (code "52") (name "Net-(D11-CATODE)") (class "Default")
      (node (ref "D11") (pin "1") (pinfunction "CATODE_1") (pintype "passive"))
      (node (ref "R28") (pin "1") (pinfunction "1_1") (pintype "passive"))
    )
    (net (code "53") (name "Net-(D12-CATODE)") (class "Default")
      (node (ref "D12") (pin "1") (pinfunction "CATODE_1") (pintype "passive"))
      (node (ref "R29") (pin "1") (pinfunction "1_1") (pintype "passive"))
    )
    (net (code "54") (name "Net-(D13-CATODE)") (class "Default")
      (node (ref "D13") (pin "1") (pinfunction "CATODE_1") (pintype "passive"))
      (node (ref "R30") (pin "1") (pinfunction "1_1") (pintype "passive"))
    )
    (net (code "55") (name "Net-(D14-CATODE)") (class "Default")
      (node (ref "D14") (pin "1") (pinfunction "CATODE_1") (pintype "passive"))
      (node (ref "R31") (pin "1") (pinfunction "1_1") (pintype "passive"))
    )
    (net (code "56") (name "Net-(DISPLAY-A1)") (class "Default")
      (node (ref "DISPLAY") (pin "41") (pinfunction "A1_41") (pintype "passive"))
      (node (ref "R64") (pin "2") (pinfunction "2_2") (pintype "passive"))
    )
    (net (code "57") (name "Net-(DISPLAY-A2)") (class "Default")
      (node (ref "DISPLAY") (pin "42") (pinfunction "A2_42") (pintype "passive"))
      (node (ref "R65") (pin "2") (pinfunction "2_2") (pintype "passive"))
    )
    (net (code "58") (name "Net-(DISPLAY-A3)") (class "Default")
      (node (ref "DISPLAY") (pin "43") (pinfunction "A3_43") (pintype "passive"))
      (node (ref "R66") (pin "2") (pinfunction "2_2") (pintype "passive"))
    )
    (net (code "59") (name "Net-(DISPLAY-C1-)") (class "Default")
      (node (ref "DISPLAY") (pin "46") (pinfunction "C1-_46") (pintype "passive"))
      (node (ref "R67") (pin "1") (pinfunction "1_1") (pintype "passive"))
    )
    (net (code "60") (name "Net-(DISPLAY-C2-)") (class "Default")
      (node (ref "DISPLAY") (pin "45") (pinfunction "C2-_45") (pintype "passive"))
      (node (ref "R69") (pin "1") (pinfunction "1_1") (pintype "passive"))
    )
    (net (code "61") (name "Net-(DISPLAY-C3-)") (class "Default")
      (node (ref "DISPLAY") (pin "44") (pinfunction "C3-_44") (pintype "passive"))
      (node (ref "R68") (pin "1") (pinfunction "1_1") (pintype "passive"))
    )
    (net (code "62") (name "Net-(DISPLAY-CAP1N)") (class "Default")
      (node (ref "C7") (pin "2") (pinfunction "2_2") (pintype "passive"))
      (node (ref "C8") (pin "2") (pinfunction "2_2") (pintype "passive"))
      (node (ref "DISPLAY") (pin "30") (pinfunction "CAP1N_30") (pintype "passive"))
    )
    (net (code "63") (name "Net-(DISPLAY-CAP1P)") (class "Default")
      (node (ref "C8") (pin "1") (pinfunction "1_1") (pintype "passive"))
      (node (ref "DISPLAY") (pin "29") (pinfunction "CAP1P_29") (pintype "passive"))
    )
    (net (code "64") (name "Net-(DISPLAY-CAP2N)") (class "Default")
      (node (ref "C9") (pin "1") (pinfunction "1_1") (pintype "passive"))
      (node (ref "DISPLAY") (pin "27") (pinfunction "CAP2N_27") (pintype "passive"))
    )
    (net (code "65") (name "Net-(DISPLAY-CAP2P)") (class "Default")
      (node (ref "C9") (pin "2") (pinfunction "2_2") (pintype "passive"))
      (node (ref "DISPLAY") (pin "28") (pinfunction "CAP2P_28") (pintype "passive"))
    )
    (net (code "66") (name "Net-(DISPLAY-CAP3P)") (class "Default")
      (node (ref "C7") (pin "1") (pinfunction "1_1") (pintype "passive"))
      (node (ref "DISPLAY") (pin "31") (pinfunction "CAP3P_31") (pintype "passive"))
    )
    (net (code "67") (name "Net-(DISPLAY-V0)") (class "Default")
      (node (ref "C14") (pin "1") (pinfunction "1_1") (pintype "passive"))
      (node (ref "DISPLAY") (pin "21") (pinfunction "V0_21") (pintype "passive"))
    )
    (net (code "68") (name "Net-(DISPLAY-V1)") (class "Default")
      (node (ref "C13") (pin "1") (pinfunction "1_1") (pintype "passive"))
      (node (ref "DISPLAY") (pin "22") (pinfunction "V1_22") (pintype "passive"))
    )
    (net (code "69") (name "Net-(DISPLAY-V2)") (class "Default")
      (node (ref "C12") (pin "1") (pinfunction "1_1") (pintype "passive"))
      (node (ref "DISPLAY") (pin "23") (pinfunction "V2_23") (pintype "passive"))
    )
    (net (code "70") (name "Net-(DISPLAY-V3)") (class "Default")
      (node (ref "C11") (pin "1") (pinfunction "1_1") (pintype "passive"))
      (node (ref "DISPLAY") (pin "24") (pinfunction "V3_24") (pintype "passive"))
    )
    (net (code "71") (name "Net-(DISPLAY-V4)") (class "Default")
      (node (ref "C10") (pin "1") (pinfunction "1_1") (pintype "passive"))
      (node (ref "DISPLAY") (pin "25") (pinfunction "V4_25") (pintype "passive"))
    )
    (net (code "72") (name "Net-(DISPLAY-VOUT)") (class "Default")
      (node (ref "C6") (pin "1") (pinfunction "1_1") (pintype "passive"))
      (node (ref "DISPLAY") (pin "32") (pinfunction "VOUT_32") (pintype "passive"))
    )
    (net (code "73") (name "Net-(J8-Pad1)") (class "Default")
      (node (ref "J8") (pin "1") (pinfunction "1_1") (pintype "passive"))
      (node (ref "J9") (pin "1") (pinfunction "1_1") (pintype "passive"))
      (node (ref "R64") (pin "1") (pinfunction "1_1") (pintype "passive"))
      (node (ref "R65") (pin "1") (pinfunction "1_1") (pintype "passive"))
      (node (ref "R66") (pin "1") (pinfunction "1_1") (pintype "passive"))
      (node (ref "R70") (pin "1") (pinfunction "1_1") (pintype "passive"))
    )
    (net (code "74") (name "Net-(T4-Base)") (class "Default")
      (node (ref "R32") (pin "2") (pinfunction "2_2") (pintype "passive"))
      (node (ref "T4") (pin "1") (pinfunction "Base_1") (pintype "passive"))
    )
    (net (code "75") (name "Net-(T5-C1_1)") (class "Default")
      (node (ref "R20") (pin "2") (pinfunction "2_2") (pintype "passive"))
      (node (ref "T5") (pin "1") (pinfunction "C1_1_1") (pintype "passive"))
      (node (ref "T5") (pin "2") (pinfunction "C1_2_2") (pintype "passive"))
    )
    (net (code "76") (name "Net-(T5-C2_1)") (class "Default")
      (node (ref "R21") (pin "2") (pinfunction "2_2") (pintype "passive"))
      (node (ref "T5") (pin "3") (pinfunction "C2_1_3") (pintype "passive"))
      (node (ref "T5") (pin "4") (pinfunction "C2_2_4") (pintype "passive"))
    )
    (net (code "77") (name "Net-(T5-C3_1)") (class "Default")
      (node (ref "R22") (pin "2") (pinfunction "2_2") (pintype "passive"))
      (node (ref "T5") (pin "5") (pinfunction "C3_1_5") (pintype "passive"))
      (node (ref "T5") (pin "6") (pinfunction "C3_2_6") (pintype "passive"))
    )
    (net (code "78") (name "Net-(T5-C4_1)") (class "Default")
      (node (ref "R23") (pin "2") (pinfunction "2_2") (pintype "passive"))
      (node (ref "T5") (pin "7") (pinfunction "C4_1_7") (pintype "passive"))
      (node (ref "T5") (pin "8") (pinfunction "C4_2_8") (pintype "passive"))
    )
    (net (code "79") (name "Net-(T6-C1_1)") (class "Default")
      (node (ref "R24") (pin "2") (pinfunction "2_2") (pintype "passive"))
      (node (ref "T6") (pin "1") (pinfunction "C1_1_1") (pintype "passive"))
      (node (ref "T6") (pin "2") (pinfunction "C1_2_2") (pintype "passive"))
    )
    (net (code "80") (name "Net-(T6-C2_1)") (class "Default")
      (node (ref "R25") (pin "2") (pinfunction "2_2") (pintype "passive"))
      (node (ref "T6") (pin "3") (pinfunction "C2_1_3") (pintype "passive"))
      (node (ref "T6") (pin "4") (pinfunction "C2_2_4") (pintype "passive"))
    )
    (net (code "81") (name "Net-(T6-C3_1)") (class "Default")
      (node (ref "R26") (pin "2") (pinfunction "2_2") (pintype "passive"))
      (node (ref "T6") (pin "5") (pinfunction "C3_1_5") (pintype "passive"))
      (node (ref "T6") (pin "6") (pinfunction "C3_2_6") (pintype "passive"))
    )
    (net (code "82") (name "Net-(T6-C4_1)") (class "Default")
      (node (ref "R27") (pin "2") (pinfunction "2_2") (pintype "passive"))
      (node (ref "T6") (pin "7") (pinfunction "C4_1_7") (pintype "passive"))
      (node (ref "T6") (pin "8") (pinfunction "C4_2_8") (pintype "passive"))
    )
    (net (code "83") (name "Net-(T7-C1_1)") (class "Default")
      (node (ref "R28") (pin "2") (pinfunction "2_2") (pintype "passive"))
      (node (ref "T7") (pin "1") (pinfunction "C1_1_1") (pintype "passive"))
      (node (ref "T7") (pin "2") (pinfunction "C1_2_2") (pintype "passive"))
    )
    (net (code "84") (name "Net-(T7-C2_1)") (class "Default")
      (node (ref "R29") (pin "2") (pinfunction "2_2") (pintype "passive"))
      (node (ref "T7") (pin "3") (pinfunction "C2_1_3") (pintype "passive"))
      (node (ref "T7") (pin "4") (pinfunction "C2_2_4") (pintype "passive"))
    )
    (net (code "85") (name "Net-(T7-C3_1)") (class "Default")
      (node (ref "R30") (pin "2") (pinfunction "2_2") (pintype "passive"))
      (node (ref "T7") (pin "5") (pinfunction "C3_1_5") (pintype "passive"))
      (node (ref "T7") (pin "6") (pinfunction "C3_2_6") (pintype "passive"))
    )
    (net (code "86") (name "Net-(T7-C4_1)") (class "Default")
      (node (ref "R31") (pin "2") (pinfunction "2_2") (pintype "passive"))
      (node (ref "T7") (pin "7") (pinfunction "C4_1_7") (pintype "passive"))
      (node (ref "T7") (pin "8") (pinfunction "C4_2_8") (pintype "passive"))
    )
    (net (code "87") (name "Net-(T14-Drain)") (class "Default")
      (node (ref "R71") (pin "1") (pinfunction "1_1") (pintype "passive"))
      (node (ref "T14") (pin "3") (pinfunction "Drain_3") (pintype "passive"))
    )
    (net (code "88") (name "Net-(T14-Gate)") (class "Default")
      (node (ref "R81") (pin "2") (pinfunction "2_2") (pintype "passive"))
      (node (ref "T14") (pin "1") (pinfunction "Gate_1") (pintype "passive"))
    )
    (net (code "89") (name "Net-(T15-Drain)") (class "Default")
      (node (ref "R72") (pin "1") (pinfunction "1_1") (pintype "passive"))
      (node (ref "T15") (pin "3") (pinfunction "Drain_3") (pintype "passive"))
    )
    (net (code "90") (name "Net-(T15-Gate)") (class "Default")
      (node (ref "R80") (pin "2") (pinfunction "2_2") (pintype "passive"))
      (node (ref "T15") (pin "1") (pinfunction "Gate_1") (pintype "passive"))
    )
    (net (code "91") (name "Net-(T16-Drain)") (class "Default")
      (node (ref "R79") (pin "1") (pinfunction "1_1") (pintype "passive"))
      (node (ref "T16") (pin "3") (pinfunction "Drain_3") (pintype "passive"))
    )
    (net (code "92") (name "Net-(U1a-Q0)") (class "Default")
      (node (ref "R33") (pin "2") (pinfunction "2_2") (pintype "passive"))
      (node (ref "U1a") (pin "3") (pinfunction "Q0_3") (pintype "passive"))
    )
    (net (code "93") (name "Net-(U1a-Q1)") (class "Default")
      (node (ref "R36") (pin "2") (pinfunction "2_2") (pintype "passive"))
      (node (ref "U1a") (pin "4") (pinfunction "Q1_4") (pintype "passive"))
    )
    (net (code "94") (name "Net-(U1a-Q2)") (class "Default")
      (node (ref "R39") (pin "2") (pinfunction "2_2") (pintype "passive"))
      (node (ref "U1a") (pin "5") (pinfunction "Q2_5") (pintype "passive"))
    )
    (net (code "95") (name "Net-(U1a-Q3)") (class "Default")
      (node (ref "R57") (pin "2") (pinfunction "2_2") (pintype "passive"))
      (node (ref "U1a") (pin "6") (pinfunction "Q3_6") (pintype "passive"))
    )
    (net (code "96") (name "Net-(U4a-Q0)") (class "Default")
      (node (ref "R34") (pin "2") (pinfunction "2_2") (pintype "passive"))
      (node (ref "U4a") (pin "3") (pinfunction "Q0_3") (pintype "passive"))
    )
    (net (code "97") (name "Net-(U4a-Q1)") (class "Default")
      (node (ref "R37") (pin "2") (pinfunction "2_2") (pintype "passive"))
      (node (ref "U4a") (pin "4") (pinfunction "Q1_4") (pintype "passive"))
    )
    (net (code "98") (name "Net-(U4a-Q2)") (class "Default")
      (node (ref "R40") (pin "2") (pinfunction "2_2") (pintype "passive"))
      (node (ref "U4a") (pin "5") (pinfunction "Q2_5") (pintype "passive"))
    )
    (net (code "99") (name "Net-(U4a-Q3)") (class "Default")
      (node (ref "R60") (pin "2") (pinfunction "2_2") (pintype "passive"))
      (node (ref "U4a") (pin "6") (pinfunction "Q3_6") (pintype "passive"))
    )
    (net (code "100") (name "Net-(U4a-Q4)") (class "Default")
      (node (ref "R41") (pin "1") (pinfunction "1_1") (pintype "passive"))
      (node (ref "U4a") (pin "10") (pinfunction "Q4_10") (pintype "passive"))
    )
    (net (code "101") (name "Net-(U4a-Q5)") (class "Default")
      (node (ref "R38") (pin "1") (pinfunction "1_1") (pintype "passive"))
      (node (ref "U4a") (pin "11") (pinfunction "Q5_11") (pintype "passive"))
    )
    (net (code "102") (name "Net-(U4a-Q6)") (class "Default")
      (node (ref "R35") (pin "1") (pinfunction "1_1") (pintype "passive"))
      (node (ref "U4a") (pin "12") (pinfunction "Q6_12") (pintype "passive"))
    )
    (net (code "103") (name "Net-(U4a-Q7)") (class "Default")
      (node (ref "R12") (pin "1") (pinfunction "1_1") (pintype "passive"))
      (node (ref "U4a") (pin "13") (pinfunction "Q7_13") (pintype "passive"))
    )
    (net (code "104") (name "unconnected-(J5-Pad4)") (class "Default")
      (node (ref "J5") (pin "4") (pinfunction "4_4") (pintype "passive"))
    )
    (net (code "105") (name "unconnected-(J6-Pad3)") (class "Default")
      (node (ref "J6") (pin "3") (pinfunction "3_3") (pintype "bidirectional"))
    )
    (net (code "106") (name "unconnected-(J6-Pad6)") (class "Default")
      (node (ref "J6") (pin "6") (pinfunction "6_6") (pintype "bidirectional"))
    )
    (net (code "107") (name "unconnected-(U1a-Q4-Pad10)") (class "Default")
      (node (ref "U1a") (pin "10") (pinfunction "Q4_10") (pintype "passive"))
    )
    (net (code "108") (name "unconnected-(U1a-Q5-Pad11)") (class "Default")
      (node (ref "U1a") (pin "11") (pinfunction "Q5_11") (pintype "passive"))
    )
    (net (code "109") (name "unconnected-(U1a-Q6-Pad12)") (class "Default")
      (node (ref "U1a") (pin "12") (pinfunction "Q6_12") (pintype "passive"))
    )
    (net (code "110") (name "unconnected-(U1a-Q7-Pad13)") (class "Default")
      (node (ref "U1a") (pin "13") (pinfunction "Q7_13") (pintype "passive"))
    )
  )
)
